# WIFI_Module.net
KiCad netlist of a schematic drawn in Altium Designer
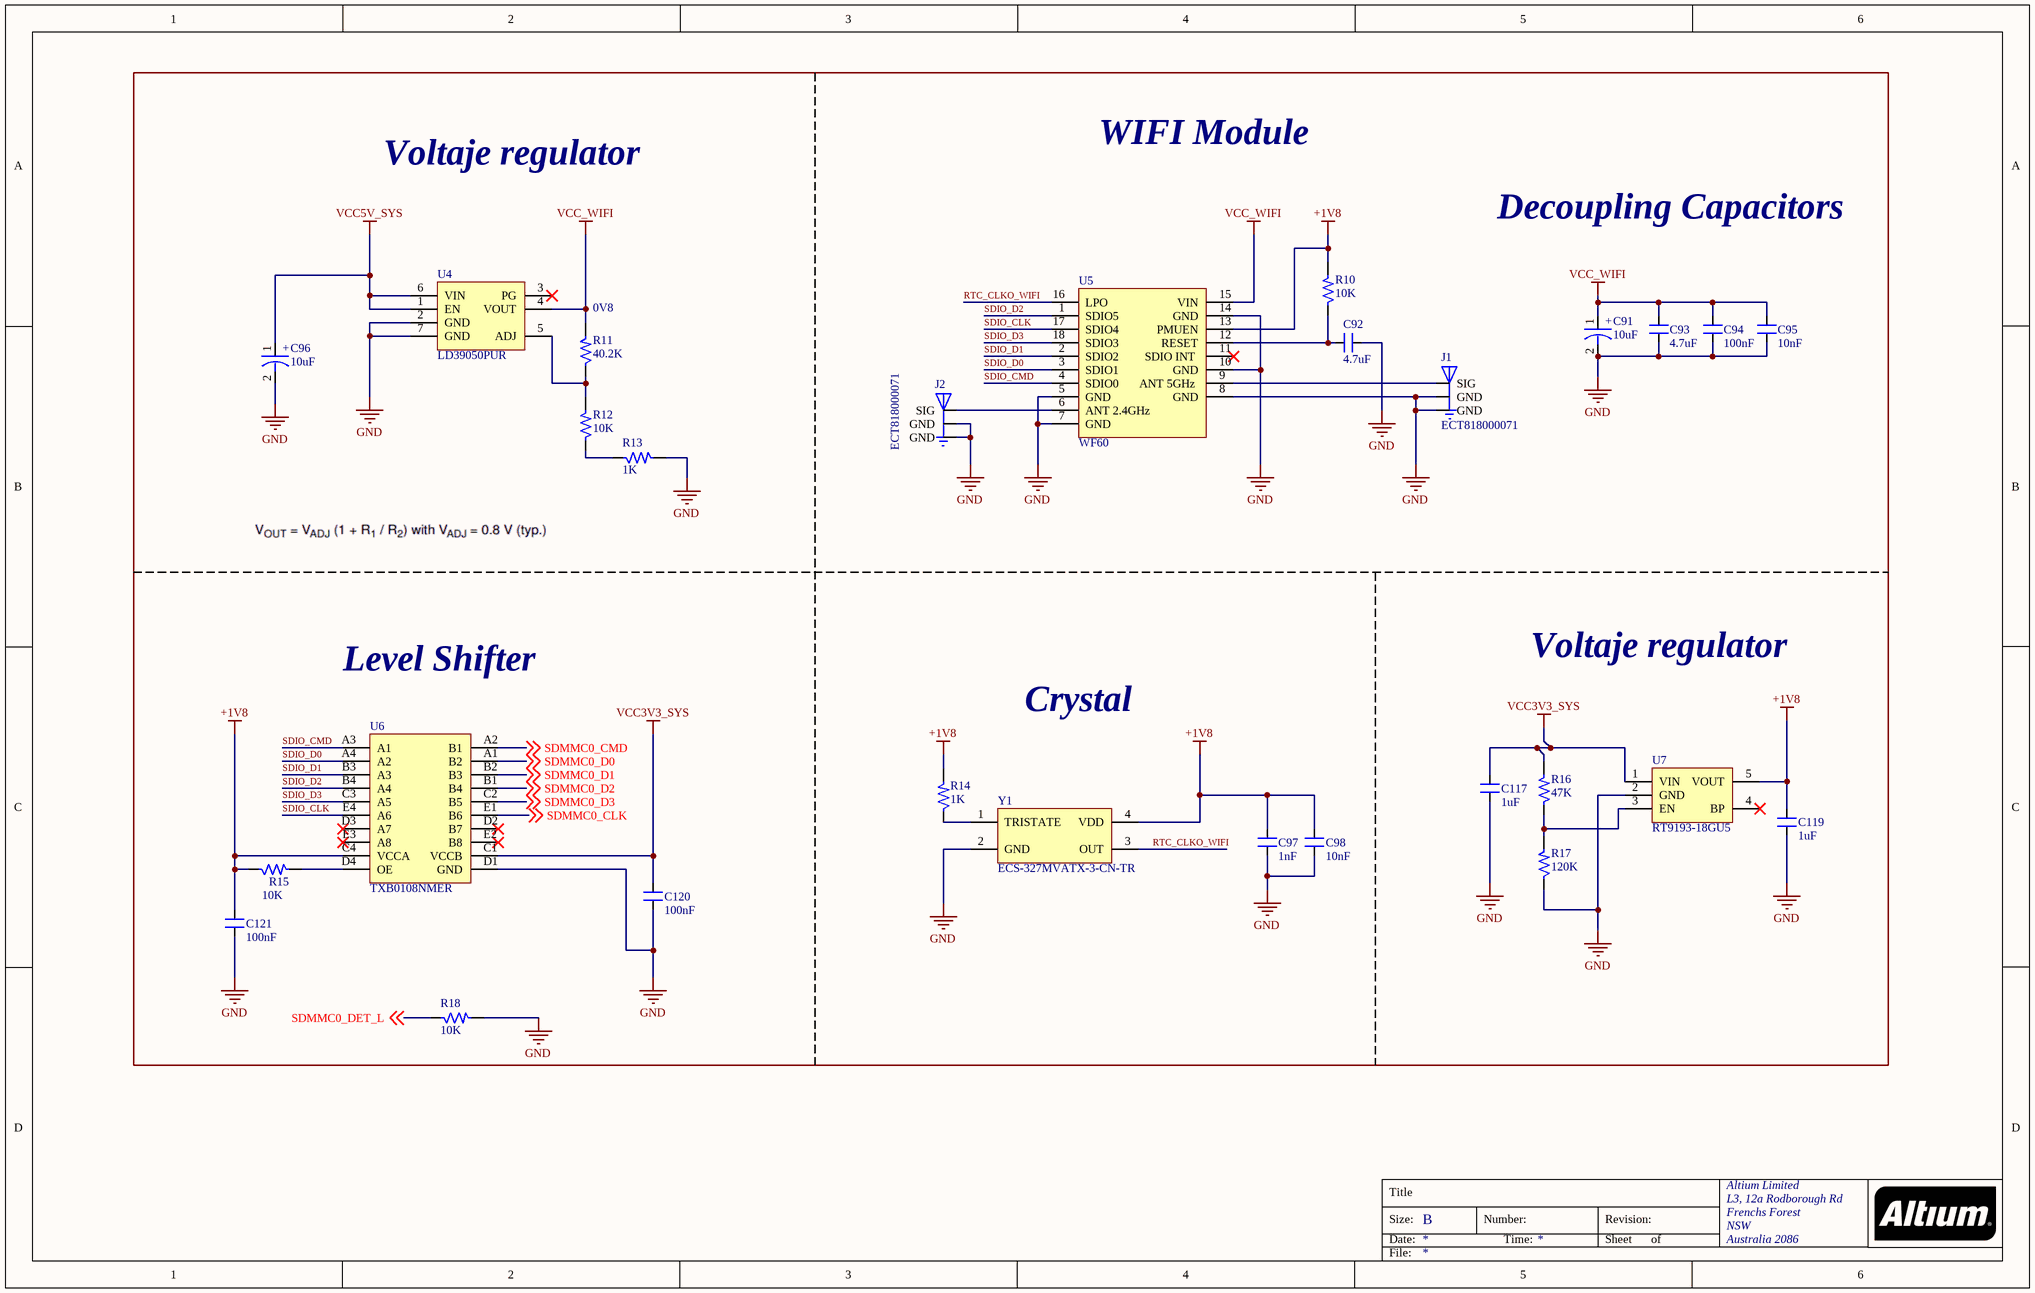
[diagram p0: WIFI_Module.SchDoc]

(export (version "E")
  (design (tool "Eeschema 10.0.6"))
  (components
    (comp (ref "C91")
      (value "10uF")
      (footprint "CAP-T_1206")
      (description "10µF Molded Tantalum Capacitors 16V 1206 (3216 Metric) 3Ohm")
      (fields
        (field (name "MANUFACTURER") "AVX Corporation")
        (field (name "MANUFACTURER PART NUMBER") "TAJA106K016SNJ")
      )
      (libsource (lib "EsteemPCB_SOM_Course_intlib") (part "CAP-P_10uF-16V-10%-1206"))
    )
    (comp (ref "C92")
      (value "4.7uF")
      (footprint "CAP_0201")
      (description "4.7µF ±20% 6.3V Ceramic Capacitor X5R 0201 (0603 Metric)")
      (fields
        (field (name "MANUFACTURER") "Murata Electronics")
        (field (name "MANUFACTURER PART NUMBER") "GRM035R60J475ME15D")
      )
      (libsource (lib "EsteemPCB_SOM_Course_intlib") (part "CAP_4.7uF-6.3V-20%-0201"))
    )
    (comp (ref "C93")
      (value "4.7uF")
      (footprint "CAP_0402")
      (description "4.7µF ±10% 10V Ceramic Capacitor X5R 0402 (1005 Metric)")
      (fields
        (field (name "MANUFACTURER") "Samsung Electro-Mechanics")
        (field (name "MANUFACTURER PART NUMBER") "CL05A475KP5NRNC")
      )
      (libsource (lib "EsteemPCB_SOM_Course_intlib") (part "CAP_4.7uF-10V-10%-0402"))
    )
    (comp (ref "C94")
      (value "100nF")
      (footprint "CAP_0402")
      (description "0.1µF ±10% 25V Ceramic Capacitor X7R 0402 (1005 Metric)")
      (fields
        (field (name "MANUFACTURER") "Walsin Technology Corporation")
        (field (name "MANUFACTURER PART NUMBER") "0402B104K250CT")
      )
      (libsource (lib "EsteemPCB_SOM_Course_intlib") (part "CAP_100nF-25V-10%-0402"))
    )
    (comp (ref "C95")
      (value "10nF")
      (footprint "CAP_0402")
      (description "10000pF ±10% 10V Ceramic Capacitor X7R 0402 (1005 Metric)")
      (fields
        (field (name "MANUFACTURER") "AVX Corporation")
        (field (name "MANUFACTURER PART NUMBER") "0402ZC103KAT2A")
      )
      (libsource (lib "EsteemPCB_SOM_Course_intlib") (part "CAP_10nF-10V-10%-0402"))
    )
    (comp (ref "C96")
      (value "10uF")
      (footprint "CAP-T_1206")
      (description "10µF Molded Tantalum Capacitors 16V 1206 (3216 Metric) 3Ohm")
      (fields
        (field (name "MANUFACTURER") "AVX Corporation")
        (field (name "MANUFACTURER PART NUMBER") "TAJA106K016SNJ")
      )
      (libsource (lib "EsteemPCB_SOM_Course_intlib") (part "CAP-P_10uF-16V-10%-1206"))
    )
    (comp (ref "C97")
      (value "1nF")
      (footprint "CAP_0402")
      (description "1000pF ±10% 10V Ceramic Capacitor X7R 0402 (1005 Metric)")
      (fields
        (field (name "MANUFACTURER") "KEMET")
        (field (name "MANUFACTURER PART NUMBER") "C0402C102K8RACTU")
      )
      (libsource (lib "EsteemPCB_SOM_Course_intlib") (part "CAP_1nF-10V-10%-0402"))
    )
    (comp (ref "C98")
      (value "10nF")
      (footprint "CAP_0402")
      (description "10000pF ±10% 10V Ceramic Capacitor X7R 0402 (1005 Metric)")
      (fields
        (field (name "MANUFACTURER") "AVX Corporation")
        (field (name "MANUFACTURER PART NUMBER") "0402ZC103KAT2A")
      )
      (libsource (lib "EsteemPCB_SOM_Course_intlib") (part "CAP_10nF-10V-10%-0402"))
    )
    (comp (ref "C117")
      (value "1uF")
      (footprint "CAP_0201")
      (description "1µF ±20% 16V Ceramic Capacitor X5R 0201 (0603 Metric)")
      (fields
        (field (name "MANUFACTURER") "Samsung Electro-Mechanics")
        (field (name "MANUFACTURER PART NUMBER") "CL03A105MO3NRNH")
      )
      (libsource (lib "EsteemPCB_SOM_Course_intlib") (part "CAP_1uF-16V-10%-0201"))
    )
    (comp (ref "C119")
      (value "1uF")
      (footprint "CAP_0201")
      (description "1µF ±20% 16V Ceramic Capacitor X5R 0201 (0603 Metric)")
      (fields
        (field (name "MANUFACTURER") "Samsung Electro-Mechanics")
        (field (name "MANUFACTURER PART NUMBER") "CL03A105MO3NRNH")
      )
      (libsource (lib "EsteemPCB_SOM_Course_intlib") (part "CAP_1uF-16V-10%-0201"))
    )
    (comp (ref "C120")
      (value "100nF")
      (footprint "CAP_0201")
      (description "0.1µF ±10% 25V Ceramic Capacitor X5R 0201 (0603 Metric)")
      (fields
        (field (name "MANUFACTURER") "TDK Corporation")
        (field (name "MANUFACTURER PART NUMBER") "C0603X5R1E104K030BB")
      )
      (libsource (lib "EsteemPCB_SOM_Course_intlib") (part "CAP_100nF-25V-10%-0201"))
    )
    (comp (ref "C121")
      (value "100nF")
      (footprint "CAP_0201")
      (description "0.1µF ±10% 25V Ceramic Capacitor X5R 0201 (0603 Metric)")
      (fields
        (field (name "MANUFACTURER") "TDK Corporation")
        (field (name "MANUFACTURER PART NUMBER") "C0603X5R1E104K030BB")
      )
      (libsource (lib "EsteemPCB_SOM_Course_intlib") (part "CAP_100nF-25V-10%-0201"))
    )
    (comp (ref "J1")
      (value "ECT818000071")
      (footprint "CON3_UFL_116_SMD_ST")
      (description "SMD RF Connectors/Coaxial Connectors RoHS")
      (fields (field (name "MANUFACTURER") "ECT"))
      (libsource (lib "EsteemPCB_SOM_Course_intlib") (part "CON-PLG_3X1-ECT818000071-ST-SMD"))
    )
    (comp (ref "J2")
      (value "ECT818000071")
      (footprint "CON3_UFL_116_SMD_ST")
      (description "SMD RF Connectors/Coaxial Connectors RoHS")
      (fields (field (name "MANUFACTURER") "ECT"))
      (libsource (lib "EsteemPCB_SOM_Course_intlib") (part "CON-PLG_3X1-ECT818000071-ST-SMD"))
    )
    (comp (ref "R10")
      (value "10K")
      (footprint "RES_0201")
      (description "10 kOhms ±1% 0.05W, 1/20W Chip Resistor 0201 (0603 Metric) Thick Film")
      (fields
        (field (name "MANUFACTURER") "Stackpole Electronics Inc")
        (field (name "MANUFACTURER PART NUMBER") "RMCF0201FT10K0")
      )
      (libsource (lib "EsteemPCB_SOM_Course_intlib") (part "RES_10K-0.05W-1%-0201"))
    )
    (comp (ref "R11")
      (value "40.2K")
      (footprint "RES_0201")
      (fields
        (field (name "MANUFACTURER") "Yageo")
        (field (name "MANUFACTURER PART NUMBER") "AC0201FR-0740K2L")
      )
      (libsource (lib "EsteemPCB_SOM_Course_intlib") (part "RES_40.2K-0.05W-1%-0201"))
    )
    (comp (ref "R12")
      (value "10K")
      (footprint "RES_0201")
      (description "10 kOhms ±1% 0.05W, 1/20W Chip Resistor 0201 (0603 Metric) Thick Film")
      (fields
        (field (name "MANUFACTURER") "Stackpole Electronics Inc")
        (field (name "MANUFACTURER PART NUMBER") "RMCF0201FT10K0")
      )
      (libsource (lib "EsteemPCB_SOM_Course_intlib") (part "RES_10K-0.05W-1%-0201"))
    )
    (comp (ref "R13")
      (value "1K")
      (footprint "RES_0402")
      (description "1 kOhms ±1% 0.1W, 1/10W Chip Resistor 0402 (1005 Metric) Anti-Sulfur Thin Film")
      (fields
        (field (name "MANUFACTURER") "Vishay Beyschlag/Draloric/BC Components")
        (field (name "MANUFACTURER PART NUMBER") "MCS04020C1001FE000")
      )
      (libsource (lib "EsteemPCB_SOM_Course_intlib") (part "RES_1K-0.1W-1%-0402"))
    )
    (comp (ref "R14")
      (value "1K")
      (footprint "RES_0201")
      (description "10 kOhms ±1% 0.05W, 1/20W Chip Resistor 0201 (0603 Metric) Thick Film")
      (fields
        (field (name "MANUFACTURER") "Stackpole Electronics Inc")
        (field (name "MANUFACTURER PART NUMBER") "RMCF0201FT10K0")
      )
      (libsource (lib "EsteemPCB_SOM_Course_intlib") (part "RES_10K-0.05W-1%-0201"))
    )
    (comp (ref "R15")
      (value "10K")
      (footprint "RES_0201")
      (description "10 kOhms ±1% 0.05W, 1/20W Chip Resistor 0201 (0603 Metric) Thick Film")
      (fields
        (field (name "MANUFACTURER") "Stackpole Electronics Inc")
        (field (name "MANUFACTURER PART NUMBER") "RMCF0201FT10K0")
      )
      (libsource (lib "EsteemPCB_SOM_Course_intlib") (part "RES_10K-0.05W-1%-0201"))
    )
    (comp (ref "R16")
      (value "47K")
      (footprint "RES_0402")
      (description "47 kOhms ±1% 0.1W, 1/10W Chip Resistor 0402 (1005 Metric) Automotive AEC-Q200 Thick Film")
      (fields
        (field (name "MANUFACTURER") "Panasonic Electronic Components")
        (field (name "MANUFACTURER PART NUMBER") "ERJ-2RKF4702X")
      )
      (libsource (lib "EsteemPCB_SOM_Course_intlib") (part "RES_47K-0.1W-1%-0402"))
    )
    (comp (ref "R17")
      (value "120K")
      (footprint "RES_0402")
      (description "120 kOhms ±1% 0.1W, 1/10W Chip Resistor 0402 (1005 Metric) Anti-Sulfur Thin Film")
      (fields
        (field (name "MANUFACTURER") "Vishay Beyschlag/Draloric/BC Components")
        (field (name "MANUFACTURER PART NUMBER") "MCS04020C1203FE000")
      )
      (libsource (lib "EsteemPCB_SOM_Course_intlib") (part "RES_120K-0.1W-1%-0402"))
    )
    (comp (ref "R18")
      (value "10K")
      (footprint "RES_0201")
      (description "10 kOhms ±1% 0.05W, 1/20W Chip Resistor 0201 (0603 Metric) Thick Film")
      (fields
        (field (name "MANUFACTURER") "Stackpole Electronics Inc")
        (field (name "MANUFACTURER PART NUMBER") "RMCF0201FT10K0")
      )
      (libsource (lib "EsteemPCB_SOM_Course_intlib") (part "RES_10K-0.05W-1%-0201"))
    )
    (comp (ref "U4")
      (value "LD39050PUR")
      (footprint "DFN-6_37.4_165_33X15_SMD")
      (description "Adjustable 5.5V 0.8V 500mA DFN-6 Linear Voltage Regulators RoHS")
      (fields (field (name "MANUFACTURER") "STMicroelectronics"))
      (libsource (lib "EsteemPCB_SOM_Course_intlib") (part "REG_5.5V-0~5.1V-0.5A-2.55W-DFN-6"))
    )
    (comp (ref "U5")
      (value "WF60")
      (footprint "MOD_WF60")
      (description "Amp’ed RF Tech presents the WF60 WiFi dual\r\nband module: 802.11abgn.")
      (fields (field (name "MANUFACTURER") "Amp’ed"))
      (libsource (lib "EsteemPCB_SOM_Course_intlib") (part "MOD_WF60-SMD"))
    )
    (comp (ref "U6")
      (value "TXB0108NMER")
      (footprint "NFBGA_31.4_125.9X102.36")
      (fields (field (name "MANUFACTURER") "Texas Instruments"))
      (libsource (lib "EsteemPCB_SOM_Course_intlib") (part "IC_TXB0108NMER"))
    )
    (comp (ref "U7")
      (value "RT9193-18GU5")
      (footprint "SC70-5")
      (description "Linear Voltage Regulator IC 1 Output 300mA SC-70-5")
      (fields (field (name "MANUFACTURER") "Richtek USA Inc."))
      (libsource (lib "EsteemPCB_SOM_Course_intlib") (part "REG_1.8V-300mA-5.5V-SC70-5"))
    )
    (comp (ref "Y1")
      (value "ECS-327MVATX-3-CN-TR")
      (footprint "XTAL_57_35X31_SMD")
      (description "32.768kHz XO (Standard) CMOS Oscillator 1.6V ~ 3.6V Enable/Disable 4-SMD, No Lead")
      (fields (field (name "MANUFACTURER") "ECS INC"))
      (libsource (lib "EsteemPCB_SOM_Course_intlib") (part "XTAL_ECS-327MVATX-2-CN-TR"))
    )
  )
  (nets
    (net (code "1") (name "+1V8") (class "Default")
      (node (ref "C119") (pin "2") (pinfunction "2_2") (pintype "passive"))
      (node (ref "C121") (pin "2") (pinfunction "2_2") (pintype "passive"))
      (node (ref "C97") (pin "2") (pinfunction "2_2") (pintype "passive"))
      (node (ref "C98") (pin "2") (pinfunction "2_2") (pintype "passive"))
      (node (ref "R10") (pin "2") (pinfunction "2_2") (pintype "passive"))
      (node (ref "R14") (pin "2") (pinfunction "2_2") (pintype "passive"))
      (node (ref "R15") (pin "1") (pinfunction "1_1") (pintype "passive"))
      (node (ref "U5") (pin "13") (pinfunction "PMUEN_13") (pintype "passive"))
      (node (ref "U6") (pin "C4") (pinfunction "VCCA_C4") (pintype "passive"))
      (node (ref "U7") (pin "5") (pinfunction "VOUT_5") (pintype "passive"))
      (node (ref "Y1") (pin "4") (pinfunction "VDD_4") (pintype "passive"))
    )
    (net (code "2") (name "/RTC_CLKO_WIFI") (class "Default")
      (node (ref "U5") (pin "16") (pinfunction "LPO_16") (pintype "passive"))
      (node (ref "Y1") (pin "3") (pinfunction "OUT_3") (pintype "passive"))
    )
    (net (code "3") (name "/SDIO_CLK") (class "Default")
      (node (ref "U5") (pin "17") (pinfunction "SDIO4_17") (pintype "passive"))
      (node (ref "U6") (pin "E4") (pinfunction "A6_E4") (pintype "passive"))
    )
    (net (code "4") (name "/SDIO_CMD") (class "Default")
      (node (ref "U5") (pin "4") (pinfunction "SDIO0_4") (pintype "passive"))
      (node (ref "U6") (pin "A3") (pinfunction "A1_A3") (pintype "passive"))
    )
    (net (code "5") (name "/SDIO_D0") (class "Default")
      (node (ref "U5") (pin "3") (pinfunction "SDIO1_3") (pintype "passive"))
      (node (ref "U6") (pin "A4") (pinfunction "A2_A4") (pintype "passive"))
    )
    (net (code "6") (name "/SDIO_D1") (class "Default")
      (node (ref "U5") (pin "2") (pinfunction "SDIO2_2") (pintype "passive"))
      (node (ref "U6") (pin "B3") (pinfunction "A3_B3") (pintype "passive"))
    )
    (net (code "7") (name "/SDIO_D2") (class "Default")
      (node (ref "U5") (pin "1") (pinfunction "SDIO5_1") (pintype "passive"))
      (node (ref "U6") (pin "B4") (pinfunction "A4_B4") (pintype "passive"))
    )
    (net (code "8") (name "/SDIO_D3") (class "Default")
      (node (ref "U5") (pin "18") (pinfunction "SDIO3_18") (pintype "passive"))
      (node (ref "U6") (pin "C3") (pinfunction "A5_C3") (pintype "passive"))
    )
    (net (code "9") (name "GND") (class "Default")
      (node (ref "C117") (pin "1") (pinfunction "1_1") (pintype "passive"))
      (node (ref "C119") (pin "1") (pinfunction "1_1") (pintype "passive"))
      (node (ref "C120") (pin "1") (pinfunction "1_1") (pintype "passive"))
      (node (ref "C121") (pin "1") (pinfunction "1_1") (pintype "passive"))
      (node (ref "C91") (pin "2") (pinfunction "2_2") (pintype "passive"))
      (node (ref "C92") (pin "2") (pinfunction "2_2") (pintype "passive"))
      (node (ref "C93") (pin "1") (pinfunction "1_1") (pintype "passive"))
      (node (ref "C94") (pin "1") (pinfunction "1_1") (pintype "passive"))
      (node (ref "C95") (pin "1") (pinfunction "1_1") (pintype "passive"))
      (node (ref "C96") (pin "2") (pinfunction "2_2") (pintype "passive"))
      (node (ref "C97") (pin "1") (pinfunction "1_1") (pintype "passive"))
      (node (ref "C98") (pin "1") (pinfunction "1_1") (pintype "passive"))
      (node (ref "J1") (pin "1") (pinfunction "GND_1") (pintype "passive"))
      (node (ref "J1") (pin "3") (pinfunction "GND_3") (pintype "passive"))
      (node (ref "J2") (pin "1") (pinfunction "GND_1") (pintype "passive"))
      (node (ref "J2") (pin "3") (pinfunction "GND_3") (pintype "passive"))
      (node (ref "R13") (pin "2") (pinfunction "2_2") (pintype "passive"))
      (node (ref "R17") (pin "1") (pinfunction "1_1") (pintype "passive"))
      (node (ref "R18") (pin "2") (pinfunction "2_2") (pintype "passive"))
      (node (ref "U4") (pin "2") (pinfunction "GND_2") (pintype "passive"))
      (node (ref "U4") (pin "7") (pinfunction "GND_7") (pintype "passive"))
      (node (ref "U5") (pin "10") (pinfunction "GND_10") (pintype "passive"))
      (node (ref "U5") (pin "14") (pinfunction "GND_14") (pintype "passive"))
      (node (ref "U5") (pin "5") (pinfunction "GND_5") (pintype "passive"))
      (node (ref "U5") (pin "7") (pinfunction "GND_7") (pintype "passive"))
      (node (ref "U5") (pin "8") (pinfunction "GND_8") (pintype "passive"))
      (node (ref "U6") (pin "D1") (pinfunction "GND_D1") (pintype "passive"))
      (node (ref "U7") (pin "2") (pinfunction "GND_2") (pintype "passive"))
      (node (ref "Y1") (pin "2") (pinfunction "GND_2") (pintype "passive"))
    )
    (net (code "10") (name "Net-(J1-SIG)") (class "Default")
      (node (ref "J1") (pin "2") (pinfunction "SIG_2") (pintype "passive"))
      (node (ref "U5") (pin "9") (pinfunction "ANT_5GHz_9") (pintype "passive"))
    )
    (net (code "11") (name "Net-(J2-SIG)") (class "Default")
      (node (ref "J2") (pin "2") (pinfunction "SIG_2") (pintype "passive"))
      (node (ref "U5") (pin "6") (pinfunction "ANT_2.4GHz_6") (pintype "passive"))
    )
    (net (code "12") (name "Net-(R12-Pad1)") (class "Default")
      (node (ref "R12") (pin "1") (pinfunction "1_1") (pintype "passive"))
      (node (ref "R13") (pin "1") (pinfunction "1_1") (pintype "passive"))
    )
    (net (code "13") (name "Net-(U4-ADJ)") (class "Default")
      (node (ref "R11") (pin "1") (pinfunction "1_1") (pintype "passive"))
      (node (ref "R12") (pin "2") (pinfunction "2_2") (pintype "passive"))
      (node (ref "U4") (pin "5") (pinfunction "ADJ_5") (pintype "passive"))
    )
    (net (code "14") (name "Net-(U5-RESET)") (class "Default")
      (node (ref "C92") (pin "1") (pinfunction "1_1") (pintype "passive"))
      (node (ref "R10") (pin "1") (pinfunction "1_1") (pintype "passive"))
      (node (ref "U5") (pin "12") (pinfunction "RESET_12") (pintype "passive"))
    )
    (net (code "15") (name "Net-(U6-OE)") (class "Default")
      (node (ref "R15") (pin "2") (pinfunction "2_2") (pintype "passive"))
      (node (ref "U6") (pin "D4") (pinfunction "OE_D4") (pintype "passive"))
    )
    (net (code "16") (name "Net-(U7-EN)") (class "Default")
      (node (ref "R16") (pin "1") (pinfunction "1_1") (pintype "passive"))
      (node (ref "R17") (pin "2") (pinfunction "2_2") (pintype "passive"))
      (node (ref "U7") (pin "3") (pinfunction "EN_3") (pintype "passive"))
    )
    (net (code "17") (name "Net-(Y1-TRISTATE)") (class "Default")
      (node (ref "R14") (pin "1") (pinfunction "1_1") (pintype "passive"))
      (node (ref "Y1") (pin "1") (pinfunction "TRISTATE_1") (pintype "passive"))
    )
    (net (code "18") (name "SDMMC0_CLK") (class "Default")
      (node (ref "U6") (pin "E1") (pinfunction "B6_E1") (pintype "passive"))
    )
    (net (code "19") (name "SDMMC0_CMD") (class "Default")
      (node (ref "U6") (pin "A2") (pinfunction "B1_A2") (pintype "passive"))
    )
    (net (code "20") (name "SDMMC0_D0") (class "Default")
      (node (ref "U6") (pin "A1") (pinfunction "B2_A1") (pintype "passive"))
    )
    (net (code "21") (name "SDMMC0_D1") (class "Default")
      (node (ref "U6") (pin "B2") (pinfunction "B3_B2") (pintype "passive"))
    )
    (net (code "22") (name "SDMMC0_D2") (class "Default")
      (node (ref "U6") (pin "B1") (pinfunction "B4_B1") (pintype "passive"))
    )
    (net (code "23") (name "SDMMC0_D3") (class "Default")
      (node (ref "U6") (pin "C2") (pinfunction "B5_C2") (pintype "passive"))
    )
    (net (code "24") (name "SDMMC0_DET_L") (class "Default")
      (node (ref "R18") (pin "1") (pinfunction "1_1") (pintype "passive"))
    )
    (net (code "25") (name "VCC3V3_SYS") (class "Default")
      (node (ref "C117") (pin "2") (pinfunction "2_2") (pintype "passive"))
      (node (ref "C120") (pin "2") (pinfunction "2_2") (pintype "passive"))
      (node (ref "R16") (pin "2") (pinfunction "2_2") (pintype "passive"))
      (node (ref "U6") (pin "C1") (pinfunction "VCCB_C1") (pintype "passive"))
      (node (ref "U7") (pin "1") (pinfunction "VIN_1") (pintype "passive"))
    )
    (net (code "26") (name "VCC5V_SYS") (class "Default")
      (node (ref "C96") (pin "1") (pinfunction "1_1") (pintype "passive"))
      (node (ref "U4") (pin "1") (pinfunction "EN_1") (pintype "passive"))
      (node (ref "U4") (pin "6") (pinfunction "VIN_6") (pintype "passive"))
    )
    (net (code "27") (name "VCC_WIFI") (class "Default")
      (node (ref "C91") (pin "1") (pinfunction "1_1") (pintype "passive"))
      (node (ref "C93") (pin "2") (pinfunction "2_2") (pintype "passive"))
      (node (ref "C94") (pin "2") (pinfunction "2_2") (pintype "passive"))
      (node (ref "C95") (pin "2") (pinfunction "2_2") (pintype "passive"))
      (node (ref "R11") (pin "2") (pinfunction "2_2") (pintype "passive"))
      (node (ref "U4") (pin "4") (pinfunction "VOUT_4") (pintype "passive"))
      (node (ref "U5") (pin "15") (pinfunction "VIN_15") (pintype "passive"))
    )
    (net (code "28") (name "unconnected-(U4-PG-Pad3)") (class "Default")
      (node (ref "U4") (pin "3") (pinfunction "PG_3") (pintype "passive+no_connect"))
    )
    (net (code "29") (name "unconnected-(U5-SDIO_INT-Pad11)") (class "Default")
      (node (ref "U5") (pin "11") (pinfunction "SDIO_INT_11") (pintype "passive+no_connect"))
    )
    (net (code "30") (name "unconnected-(U6-A7-PadD3)") (class "Default")
      (node (ref "U6") (pin "D3") (pinfunction "A7_D3") (pintype "passive+no_connect"))
    )
    (net (code "31") (name "unconnected-(U6-A8-PadE3)") (class "Default")
      (node (ref "U6") (pin "E3") (pinfunction "A8_E3") (pintype "passive+no_connect"))
    )
    (net (code "32") (name "unconnected-(U6-B7-PadD2)") (class "Default")
      (node (ref "U6") (pin "D2") (pinfunction "B7_D2") (pintype "passive+no_connect"))
    )
    (net (code "33") (name "unconnected-(U6-B8-PadE2)") (class "Default")
      (node (ref "U6") (pin "E2") (pinfunction "B8_E2") (pintype "passive+no_connect"))
    )
    (net (code "34") (name "unconnected-(U7-BP-Pad4)") (class "Default")
      (node (ref "U7") (pin "4") (pinfunction "BP_4") (pintype "passive+no_connect"))
    )
  )
)
